# power_supply.net
KiCad netlist of a schematic drawn in Altium Designer
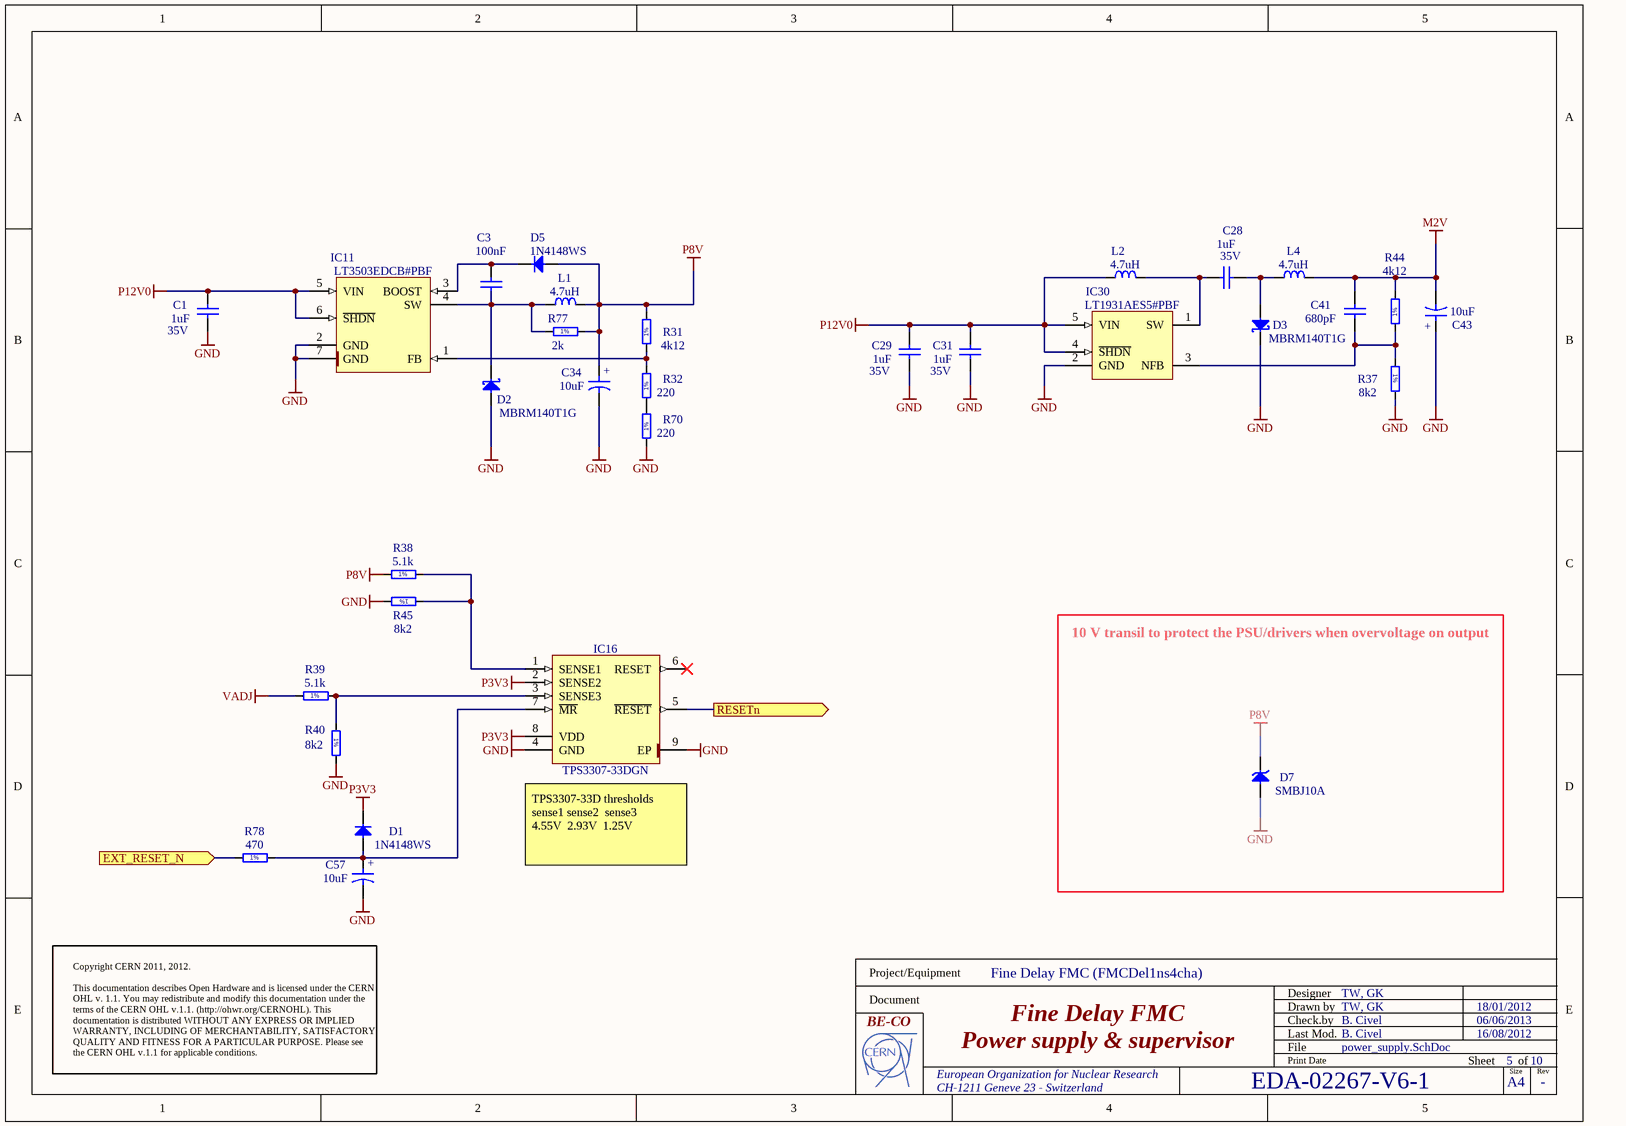
[diagram p0: power_supply.SchDoc]

(export (version "E")
  (design (tool "Eeschema 10.0.6"))
  (components
    (comp (ref "C1")
      (value "1uF")
      (footprint "CAPC2012X140N")
      (description "Non-polarised capacitor")
      (fields
        (field (name "PART NUMBER") "CC0805_1UF_35V_20%_X7R")
        (field (name "VOLTAGE") "35V")
        (field (name "TOLERANCE") "±20%")
        (field (name "AUTHOR") "CERN DEM JLC")
      )
      (libsource (lib "Capacitors") (part "Capacitor - non polarized"))
    )
    (comp (ref "C3")
      (value "100nF")
      (footprint "CAPC1608X87N")
      (description "Non-polarised capacitor")
      (fields
        (field (name "PART NUMBER") "CC0603_100NF_50V_10%_X7R")
        (field (name "VOLTAGE") "50V")
        (field (name "AUTHOR") "CERN DEM JLC")
      )
      (libsource (lib "Capacitors") (part "Capacitor - non polarized"))
    )
    (comp (ref "C28")
      (value "1uF")
      (footprint "CAPC2012X140N")
      (description "Non-polarised capacitor")
      (fields
        (field (name "PART NUMBER") "CC0805_1UF_35V_20%_X7R")
        (field (name "VOLTAGE") "35V")
        (field (name "TOLERANCE") "±20%")
        (field (name "AUTHOR") "CERN DEM JLC")
      )
      (libsource (lib "Capacitors") (part "Capacitor - non polarized"))
    )
    (comp (ref "C29")
      (value "1uF")
      (footprint "CAPC2012X140N")
      (description "Non-polarised capacitor")
      (fields
        (field (name "PART NUMBER") "CC0805_1UF_35V_20%_X7R")
        (field (name "VOLTAGE") "35V")
        (field (name "TOLERANCE") "±20%")
        (field (name "AUTHOR") "CERN DEM JLC")
      )
      (libsource (lib "Capacitors") (part "Capacitor - non polarized"))
    )
    (comp (ref "C31")
      (value "1uF")
      (footprint "CAPC2012X140N")
      (description "Non-polarised capacitor")
      (fields
        (field (name "PART NUMBER") "CC0805_1UF_35V_20%_X7R")
        (field (name "VOLTAGE") "35V")
        (field (name "TOLERANCE") "±20%")
        (field (name "AUTHOR") "CERN DEM JLC")
      )
      (libsource (lib "Capacitors") (part "Capacitor - non polarized"))
    )
    (comp (ref "C34")
      (value "10uF")
      (footprint "CAPMP3528X210N")
      (description "Polarised capacitor")
      (fields
        (field (name "PART NUMBER") "CTE3528-21_10UF_16V_20%_SANYO_TQC")
        (field (name "VOLTAGE") "16V")
        (field (name "AUTHOR") "CERN DEM JLC")
      )
      (libsource (lib "Capacitors") (part "Capacitor - polarized"))
    )
    (comp (ref "C41")
      (value "680pF")
      (footprint "CAPC1608X87N")
      (description "Non-polarised capacitor")
      (fields
        (field (name "PART NUMBER") "CC0603_680PF_50V_5%_NP0")
        (field (name "VOLTAGE") "50V")
        (field (name "AUTHOR") "CERN DEM JLC")
      )
      (libsource (lib "Capacitors") (part "Capacitor - non polarized"))
    )
    (comp (ref "C43")
      (value "10uF")
      (footprint "CAPMP3528X210N")
      (description "Polarised capacitor")
      (fields
        (field (name "PART NUMBER") "CTE3528-21_10UF_16V_20%_SANYO_TQC")
        (field (name "VOLTAGE") "16V")
        (field (name "AUTHOR") "CERN DEM JLC")
      )
      (libsource (lib "Capacitors") (part "Capacitor - polarized"))
    )
    (comp (ref "C57")
      (value "10uF")
      (footprint "CAPMP3528X210N")
      (description "Polarised capacitor")
      (fields
        (field (name "PART NUMBER") "CTE3528-21_10UF_16V_20%_SANYO_TQC")
        (field (name "VOLTAGE") "16V")
        (field (name "AUTHOR") "CERN DEM JLC")
      )
      (libsource (lib "Capacitors") (part "Capacitor - polarized"))
    )
    (comp (ref "D1")
      (value "1N4148WS")
      (footprint "SODFL2512X100N")
      (description "Diode")
      (fields
        (field (name "VOLTAGE") "75V")
        (field (name "POWER") "150mA")
        (field (name "AUTHOR") "CERN DEM JLC")
      )
      (libsource (lib "ICs And Semiconductors") (part "Diode"))
    )
    (comp (ref "D2")
      (value "MBRM140T1G")
      (footprint "ONSEMI_POWERMITE")
      (description "Schottky Diode")
      (fields
        (field (name "VOLTAGE") "40V")
        (field (name "POWER") "1A")
        (field (name "AUTHOR") "CERN DEM JLC")
      )
      (libsource (lib "ICs And Semiconductors") (part "Diode Schottky"))
    )
    (comp (ref "D3")
      (value "MBRM140T1G")
      (footprint "ONSEMI_POWERMITE")
      (description "Schottky Diode")
      (fields
        (field (name "VOLTAGE") "40V")
        (field (name "POWER") "1A")
        (field (name "AUTHOR") "CERN DEM JLC")
      )
      (libsource (lib "ICs And Semiconductors") (part "Diode Schottky"))
    )
    (comp (ref "D5")
      (value "1N4148WS")
      (footprint "SODFL2512X100N")
      (description "Diode")
      (fields
        (field (name "VOLTAGE") "75V")
        (field (name "POWER") "150mA")
        (field (name "AUTHOR") "CERN DEM JLC")
      )
      (libsource (lib "ICs And Semiconductors") (part "Diode"))
    )
    (comp (ref "D7")
      (value "SMBJ10A")
      (footprint "DIOM5336X265N")
      (description "Zener Diode")
      (fields
        (field (name "VOLTAGE") "10V")
        (field (name "POWER") "600W")
        (field (name "AUTHOR") "CERN DEM JLC")
      )
      (libsource (lib "ICs And Semiconductors") (part "Diode Zener"))
    )
    (comp (ref "IC11")
      (value "LT3503EDCB#PBF")
      (footprint "SON50P300X200X80-7N-R175X145")
      (description "1A, 2.2MHz Step-Down Switching Regulator")
      (fields (field (name "MANUFACTURER") "LINEAR TECHNOLOGY") (field (name "AUTHOR") "CERN DEM JLC"))
      (libsource (lib "ICs And Semiconductors") (part "LT3503"))
    )
    (comp (ref "IC16")
      (value "TPS3307-33DGN")
      (footprint "SOP65P490X110-9N-R157X189")
      (description "Triple Processor Supervisors")
      (fields (field (name "MANUFACTURER") "TEXAS INSTRUMENTS") (field (name "AUTHOR") "CERN DEM JLC"))
      (libsource (lib "ICs And Semiconductors") (part "TPS3307-xxDGN"))
    )
    (comp (ref "IC30")
      (value "LT1931AES5#PBF")
      (footprint "SOT95P280X100-5N")
      (description "1.2MHz/2.2MHz Inverting DC/DC Converters in ThinSOT")
      (fields (field (name "MANUFACTURER") "LINEAR TECHNOLOGY") (field (name "AUTHOR") "CERN DEM JLC"))
      (libsource (lib "ICs And Semiconductors") (part "LT1931"))
    )
    (comp (ref "L1")
      (value "4.7uH")
      (footprint "IND_TDK_VLCF5020-1")
      (description "Inductor")
      (fields
        (field (name "PART NUMBER") "IND_4.7UH_30%_TDK_VLCF5020-1")
        (field (name "POWER") "2.09A")
        (field (name "AUTHOR") "CERN DEM JLC")
      )
      (libsource (lib "Inductors & Transformers") (part "Inductor"))
    )
    (comp (ref "L2")
      (value "4.7uH")
      (footprint "IND_TDK_VLCF5020-1")
      (description "Inductor")
      (fields
        (field (name "PART NUMBER") "IND_4.7UH_30%_TDK_VLCF5020-1")
        (field (name "POWER") "2.09A")
        (field (name "AUTHOR") "CERN DEM JLC")
      )
      (libsource (lib "Inductors & Transformers") (part "Inductor"))
    )
    (comp (ref "L4")
      (value "4.7uH")
      (footprint "IND_TDK_VLCF5020-1")
      (description "Inductor")
      (fields
        (field (name "PART NUMBER") "IND_4.7UH_30%_TDK_VLCF5020-1")
        (field (name "POWER") "2.09A")
        (field (name "AUTHOR") "CERN DEM JLC")
      )
      (libsource (lib "Inductors & Transformers") (part "Inductor"))
    )
    (comp (ref "R31")
      (value "4k12")
      (footprint "RESC1608X55N")
      (description "Resistor - 1%")
      (fields
        (field (name "PART NUMBER") "R0603_4K12_1%_0.1W_100PPM")
        (field (name "POWER") "0.1W")
        (field (name "AUTHOR") "CERN DEM JLC")
      )
      (libsource (lib "Resistors") (part "Resistor - 1%"))
    )
    (comp (ref "R32")
      (value "220")
      (footprint "RESC1608X55N")
      (description "Resistor - 1%")
      (fields
        (field (name "PART NUMBER") "R0603_220R_1%_0.1W_100PPM")
        (field (name "POWER") "0.1W")
        (field (name "AUTHOR") "CERN DEM JLC")
      )
      (libsource (lib "Resistors") (part "Resistor - 1%"))
    )
    (comp (ref "R37")
      (value "8k2")
      (footprint "RESC1608X55N")
      (description "Resistor - 1%")
      (fields
        (field (name "PART NUMBER") "R0603_8K2_1%_0.1W_100PPM")
        (field (name "POWER") "0.1W")
        (field (name "AUTHOR") "CERN DEM JLC")
      )
      (libsource (lib "Resistors") (part "Resistor - 1%"))
    )
    (comp (ref "R38")
      (value "5.1k")
      (footprint "RESC1608X55N")
      (description "Resistor - 1%")
      (fields
        (field (name "PART NUMBER") "R0603_5K1_1%_0.1W_100PPM")
        (field (name "POWER") "0.1W")
        (field (name "AUTHOR") "CERN DEM JLC")
      )
      (libsource (lib "Resistors") (part "Resistor - 1%"))
    )
    (comp (ref "R39")
      (value "5.1k")
      (footprint "RESC1608X55N")
      (description "Resistor - 1%")
      (fields
        (field (name "PART NUMBER") "R0603_5K1_1%_0.1W_100PPM")
        (field (name "POWER") "0.1W")
        (field (name "AUTHOR") "CERN DEM JLC")
      )
      (libsource (lib "Resistors") (part "Resistor - 1%"))
    )
    (comp (ref "R40")
      (value "8k2")
      (footprint "RESC1608X55N")
      (description "Resistor - 1%")
      (fields
        (field (name "PART NUMBER") "R0603_8K2_1%_0.1W_100PPM")
        (field (name "POWER") "0.1W")
        (field (name "AUTHOR") "CERN DEM JLC")
      )
      (libsource (lib "Resistors") (part "Resistor - 1%"))
    )
    (comp (ref "R44")
      (value "4k12")
      (footprint "RESC1608X55N")
      (description "Resistor - 1%")
      (fields
        (field (name "PART NUMBER") "R0603_4K12_1%_0.1W_100PPM")
        (field (name "POWER") "0.1W")
        (field (name "AUTHOR") "CERN DEM JLC")
      )
      (libsource (lib "Resistors") (part "Resistor - 1%"))
    )
    (comp (ref "R45")
      (value "8k2")
      (footprint "RESC1608X55N")
      (description "Resistor - 1%")
      (fields
        (field (name "PART NUMBER") "R0603_8K2_1%_0.1W_100PPM")
        (field (name "POWER") "0.1W")
        (field (name "AUTHOR") "CERN DEM JLC")
      )
      (libsource (lib "Resistors") (part "Resistor - 1%"))
    )
    (comp (ref "R70")
      (value "220")
      (footprint "RESC1608X55N")
      (description "Resistor - 1%")
      (fields
        (field (name "PART NUMBER") "R0603_220R_1%_0.1W_100PPM")
        (field (name "POWER") "0.1W")
        (field (name "AUTHOR") "CERN DEM JLC")
      )
      (libsource (lib "Resistors") (part "Resistor - 1%"))
    )
    (comp (ref "R77")
      (value "2k")
      (footprint "RESC1608X55N")
      (description "Resistor - 1%")
      (fields
        (field (name "PART NUMBER") "R0603_2K_1%_0.1W_100PPM")
        (field (name "POWER") "0.1W")
        (field (name "AUTHOR") "CERN DEM JLC")
      )
      (libsource (lib "Resistors") (part "Resistor - 1%"))
    )
    (comp (ref "R78")
      (value "470")
      (footprint "RESC1608X55N")
      (description "Resistor - 1%")
      (fields
        (field (name "PART NUMBER") "R0603_470R_1%_0.1W_100PPM")
        (field (name "POWER") "0.1W")
        (field (name "AUTHOR") "CERN DEM JLC")
      )
      (libsource (lib "Resistors") (part "Resistor - 1%"))
    )
  )
  (nets
    (net (code "1") (name "/EXT_RESET_N") (class "Default")
      (node (ref "R78") (pin "1") (pinfunction "1_1") (pintype "passive"))
    )
    (net (code "2") (name "/RESETn") (class "Default")
      (node (ref "IC16") (pin "5") (pinfunction "~{RESET}_5") (pintype "output"))
    )
    (net (code "3") (name "GND") (class "Default")
      (node (ref "C1") (pin "2") (pinfunction "2_2") (pintype "passive"))
      (node (ref "C29") (pin "2") (pinfunction "2_2") (pintype "passive"))
      (node (ref "C31") (pin "2") (pinfunction "2_2") (pintype "passive"))
      (node (ref "C34") (pin "2") (pinfunction "2_2") (pintype "passive"))
      (node (ref "C43") (pin "1") (pinfunction "1_1") (pintype "passive"))
      (node (ref "C57") (pin "2") (pinfunction "2_2") (pintype "passive"))
      (node (ref "D2") (pin "2") (pinfunction "A_2") (pintype "passive"))
      (node (ref "D3") (pin "1") (pinfunction "C_1") (pintype "passive"))
      (node (ref "D7") (pin "2") (pinfunction "A_2") (pintype "passive"))
      (node (ref "IC11") (pin "2") (pinfunction "GND_2") (pintype "power_in"))
      (node (ref "IC11") (pin "7") (pinfunction "GND_7") (pintype "power_in"))
      (node (ref "IC16") (pin "4") (pinfunction "GND_4") (pintype "power_in"))
      (node (ref "IC16") (pin "9") (pinfunction "EP_9") (pintype "power_in"))
      (node (ref "IC30") (pin "2") (pinfunction "GND_2") (pintype "power_in"))
      (node (ref "R37") (pin "2") (pinfunction "2_2") (pintype "passive"))
      (node (ref "R40") (pin "2") (pinfunction "2_2") (pintype "passive"))
      (node (ref "R45") (pin "2") (pinfunction "2_2") (pintype "passive"))
      (node (ref "R70") (pin "1") (pinfunction "1_1") (pintype "passive"))
    )
    (net (code "4") (name "M2V") (class "Default")
      (node (ref "C41") (pin "1") (pinfunction "1_1") (pintype "passive"))
      (node (ref "C43") (pin "2") (pinfunction "2_2") (pintype "passive"))
      (node (ref "L4") (pin "2") (pinfunction "2_2") (pintype "passive"))
      (node (ref "R44") (pin "2") (pinfunction "2_2") (pintype "passive"))
    )
    (net (code "5") (name "Net-(D1-A)") (class "Default")
      (node (ref "C57") (pin "1") (pinfunction "1_1") (pintype "passive"))
      (node (ref "D1") (pin "2") (pinfunction "A_2") (pintype "passive"))
      (node (ref "IC16") (pin "7") (pinfunction "~{MR}_7") (pintype "input"))
      (node (ref "R78") (pin "2") (pinfunction "2_2") (pintype "passive"))
    )
    (net (code "6") (name "Net-(D2-C)") (class "Default")
      (node (ref "C3") (pin "1") (pinfunction "1_1") (pintype "passive"))
      (node (ref "D2") (pin "1") (pinfunction "C_1") (pintype "passive"))
      (node (ref "IC11") (pin "4") (pinfunction "SW_4") (pintype "power_in"))
      (node (ref "L1") (pin "1") (pinfunction "1_1") (pintype "passive"))
      (node (ref "R77") (pin "1") (pinfunction "1_1") (pintype "passive"))
    )
    (net (code "7") (name "Net-(D3-A)") (class "Default")
      (node (ref "C28") (pin "1") (pinfunction "1_1") (pintype "passive"))
      (node (ref "D3") (pin "2") (pinfunction "A_2") (pintype "passive"))
      (node (ref "L4") (pin "1") (pinfunction "1_1") (pintype "passive"))
    )
    (net (code "8") (name "Net-(D5-C)") (class "Default")
      (node (ref "C3") (pin "2") (pinfunction "2_2") (pintype "passive"))
      (node (ref "D5") (pin "1") (pinfunction "C_1") (pintype "passive"))
      (node (ref "IC11") (pin "3") (pinfunction "BOOST_3") (pintype "input"))
    )
    (net (code "9") (name "Net-(IC11-FB)") (class "Default")
      (node (ref "IC11") (pin "1") (pinfunction "FB_1") (pintype "input"))
      (node (ref "R31") (pin "1") (pinfunction "1_1") (pintype "passive"))
      (node (ref "R32") (pin "2") (pinfunction "2_2") (pintype "passive"))
    )
    (net (code "10") (name "Net-(IC16-SENSE1)") (class "Default")
      (node (ref "IC16") (pin "1") (pinfunction "SENSE1_1") (pintype "input"))
      (node (ref "R38") (pin "2") (pinfunction "2_2") (pintype "passive"))
      (node (ref "R45") (pin "1") (pinfunction "1_1") (pintype "passive"))
    )
    (net (code "11") (name "Net-(IC16-SENSE3)") (class "Default")
      (node (ref "IC16") (pin "3") (pinfunction "SENSE3_3") (pintype "input"))
      (node (ref "R39") (pin "2") (pinfunction "2_2") (pintype "passive"))
      (node (ref "R40") (pin "1") (pinfunction "1_1") (pintype "passive"))
    )
    (net (code "12") (name "Net-(IC30-NFB)") (class "Default")
      (node (ref "C41") (pin "2") (pinfunction "2_2") (pintype "passive"))
      (node (ref "IC30") (pin "3") (pinfunction "NFB_3") (pintype "passive"))
      (node (ref "R37") (pin "1") (pinfunction "1_1") (pintype "passive"))
      (node (ref "R44") (pin "1") (pinfunction "1_1") (pintype "passive"))
    )
    (net (code "13") (name "Net-(IC30-SW)") (class "Default")
      (node (ref "C28") (pin "2") (pinfunction "2_2") (pintype "passive"))
      (node (ref "IC30") (pin "1") (pinfunction "SW_1") (pintype "power_in"))
      (node (ref "L2") (pin "2") (pinfunction "2_2") (pintype "passive"))
    )
    (net (code "14") (name "Net-(R32-Pad1)") (class "Default")
      (node (ref "R32") (pin "1") (pinfunction "1_1") (pintype "passive"))
      (node (ref "R70") (pin "2") (pinfunction "2_2") (pintype "passive"))
    )
    (net (code "15") (name "P3V3") (class "Default")
      (node (ref "D1") (pin "1") (pinfunction "C_1") (pintype "passive"))
      (node (ref "IC16") (pin "2") (pinfunction "SENSE2_2") (pintype "input"))
      (node (ref "IC16") (pin "8") (pinfunction "VDD_8") (pintype "power_in"))
    )
    (net (code "16") (name "P8V") (class "Default")
      (node (ref "C34") (pin "1") (pinfunction "1_1") (pintype "passive"))
      (node (ref "D5") (pin "2") (pinfunction "A_2") (pintype "passive"))
      (node (ref "D7") (pin "1") (pinfunction "C_1") (pintype "passive"))
      (node (ref "L1") (pin "2") (pinfunction "2_2") (pintype "passive"))
      (node (ref "R31") (pin "2") (pinfunction "2_2") (pintype "passive"))
      (node (ref "R38") (pin "1") (pinfunction "1_1") (pintype "passive"))
      (node (ref "R77") (pin "2") (pinfunction "2_2") (pintype "passive"))
    )
    (net (code "17") (name "P12V0") (class "Default")
      (node (ref "C1") (pin "1") (pinfunction "1_1") (pintype "passive"))
      (node (ref "C29") (pin "1") (pinfunction "1_1") (pintype "passive"))
      (node (ref "C31") (pin "1") (pinfunction "1_1") (pintype "passive"))
      (node (ref "IC11") (pin "5") (pinfunction "VIN_5") (pintype "input"))
      (node (ref "IC11") (pin "6") (pinfunction "SHDN_6") (pintype "input"))
      (node (ref "IC30") (pin "4") (pinfunction "~{SHDN}_4") (pintype "input"))
      (node (ref "IC30") (pin "5") (pinfunction "VIN_5") (pintype "input"))
      (node (ref "L2") (pin "1") (pinfunction "1_1") (pintype "passive"))
    )
    (net (code "18") (name "VADJ") (class "Default")
      (node (ref "R39") (pin "1") (pinfunction "1_1") (pintype "passive"))
    )
    (net (code "19") (name "unconnected-(IC16-RESET-Pad6)") (class "Default")
      (node (ref "IC16") (pin "6") (pinfunction "RESET_6") (pintype "output+no_connect"))
    )
  )
)
